# LOGIC_FPGA.net
KiCad netlist of a schematic drawn in Altium Designer
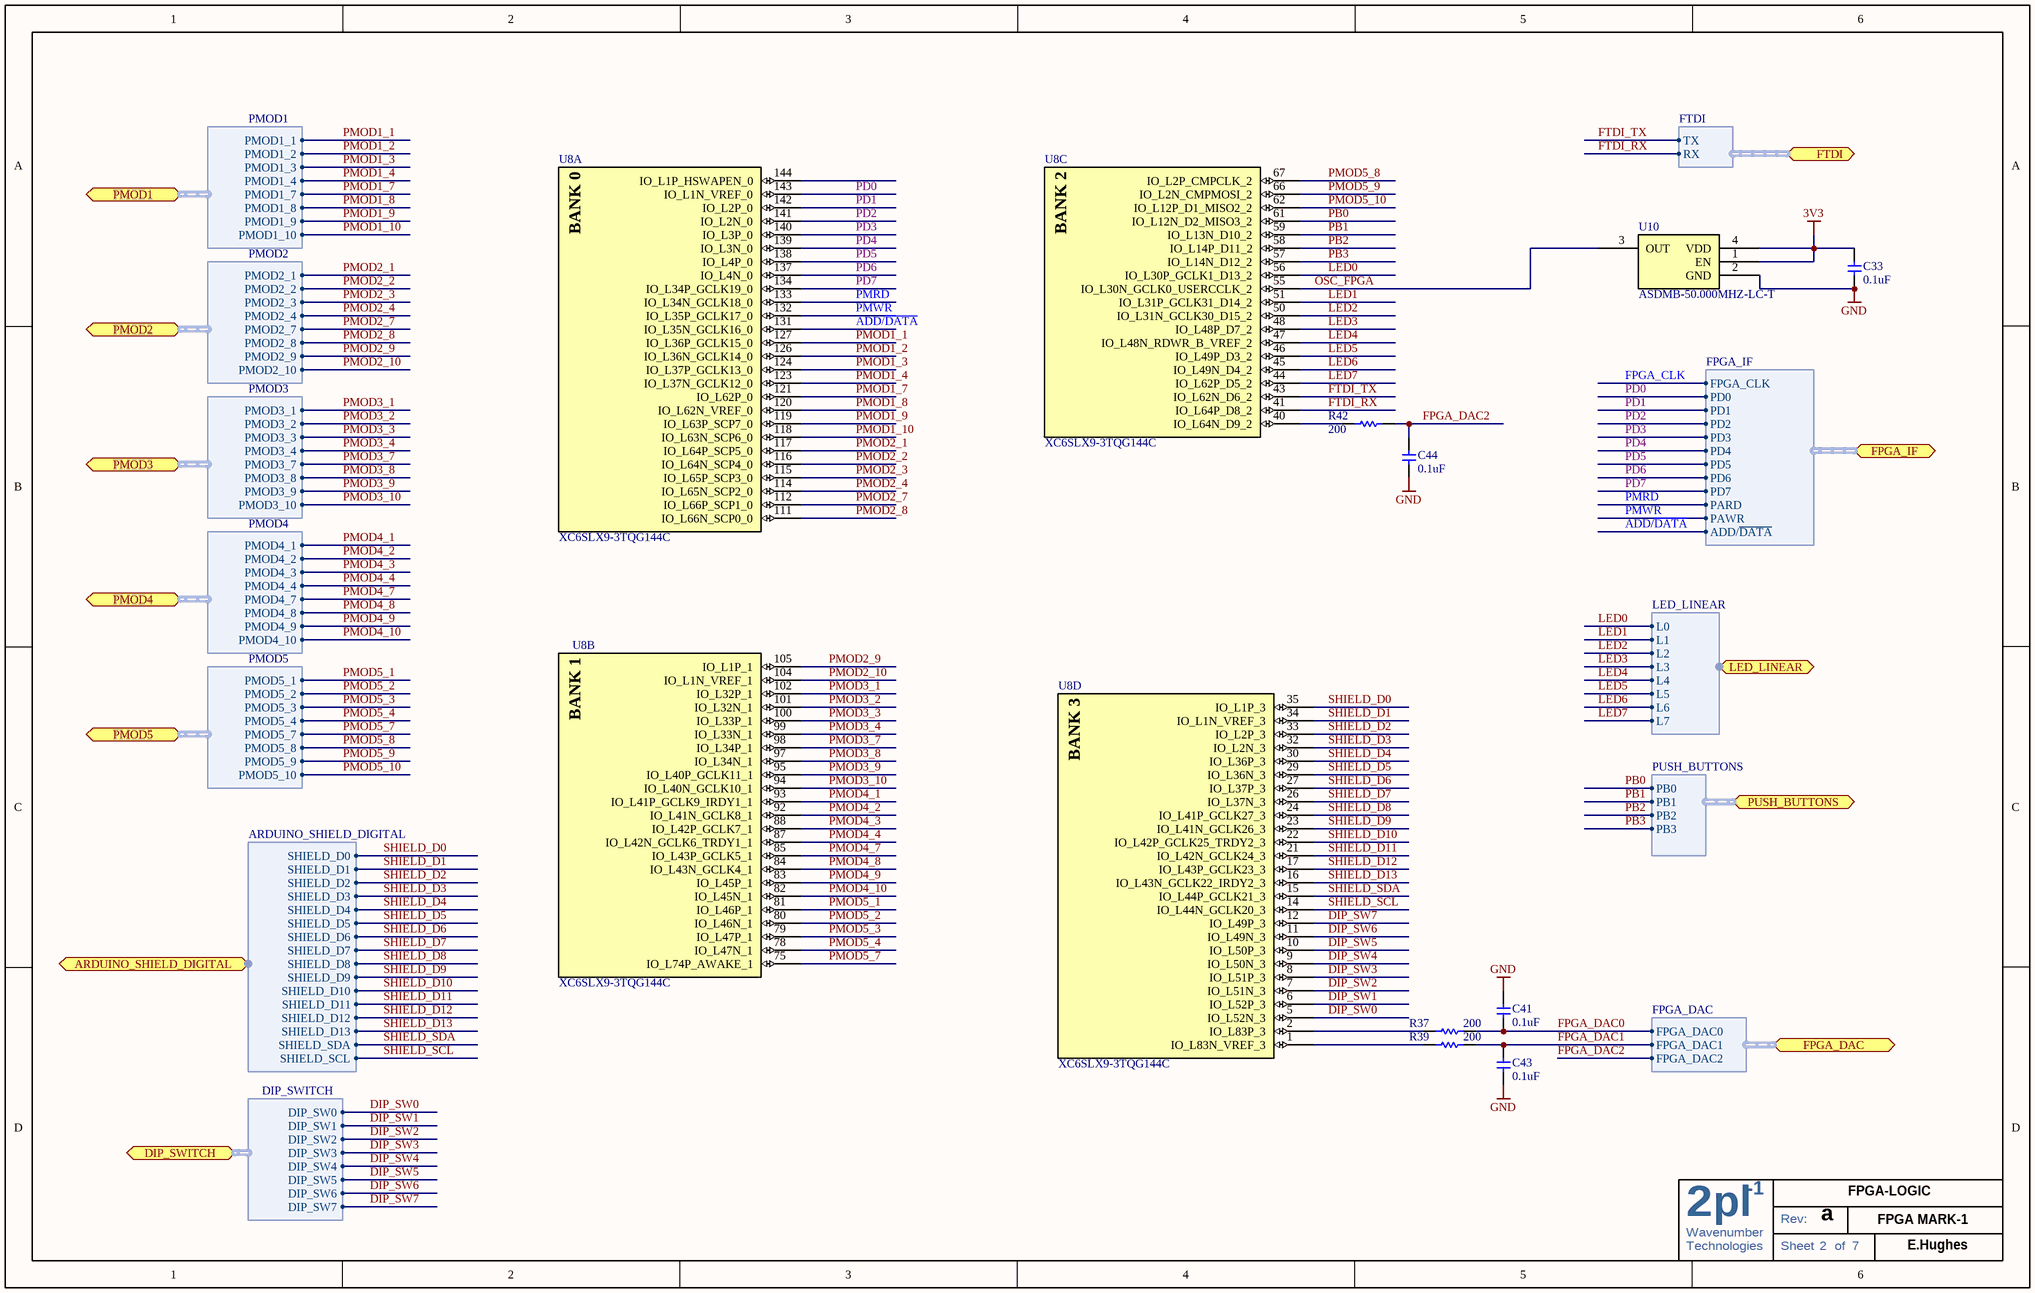
[diagram p0: LOGIC_FPGA.SchDoc]

(export (version "E")
  (design (tool "Eeschema 10.0.6"))
  (components
    (comp (ref "C33")
      (value "0.1uF")
      (footprint "C0603")
      (description "CAP CER .1UF 50V 10% X7R 0603")
      (fields
        (field (name "MANUFACTURER") "Murata Electronics North America")
        (field (name "MANUFACTURER PART NUMBER") "GRM188R71H104KA93D")
      )
      (libsource (lib "eCapacitors") (part "GRM188R71H104KA93D"))
    )
    (comp (ref "C41")
      (value "0.1uF")
      (footprint "C0603")
      (description "CAP CER .1UF 50V 10% X7R 0603")
      (fields
        (field (name "MANUFACTURER") "Murata Electronics North America")
        (field (name "MANUFACTURER PART NUMBER") "GRM188R71H104KA93D")
      )
      (libsource (lib "Capacitors") (part "GRM188R71H104KA93D"))
    )
    (comp (ref "C43")
      (value "0.1uF")
      (footprint "C0603")
      (description "CAP CER .1UF 50V 10% X7R 0603")
      (fields
        (field (name "MANUFACTURER") "Murata Electronics North America")
        (field (name "MANUFACTURER PART NUMBER") "GRM188R71H104KA93D")
      )
      (libsource (lib "Capacitors") (part "GRM188R71H104KA93D"))
    )
    (comp (ref "C44")
      (value "0.1uF")
      (footprint "C0603")
      (description "CAP CER .1UF 50V 10% X7R 0603")
      (fields
        (field (name "MANUFACTURER") "Murata Electronics North America")
        (field (name "MANUFACTURER PART NUMBER") "GRM188R71H104KA93D")
      )
      (libsource (lib "Capacitors") (part "GRM188R71H104KA93D"))
    )
    (comp (ref "R37")
      (value "200")
      (footprint "R0603")
      (description "RES 200 OHM 1/10W 1% 0603 SMD")
      (fields
        (field (name "MANUFACTURER") "Panasonic - ECG")
        (field (name "MANUFACTURER PART NUMBER") "ERJ-3EKF2000V")
      )
      (libsource (lib "eResistors") (part "ERJ-3EKF2000V"))
    )
    (comp (ref "R39")
      (value "200")
      (footprint "R0603")
      (description "RES 200 OHM 1/10W 1% 0603 SMD")
      (fields
        (field (name "MANUFACTURER") "Panasonic - ECG")
        (field (name "MANUFACTURER PART NUMBER") "ERJ-3EKF2000V")
      )
      (libsource (lib "eResistors") (part "ERJ-3EKF2000V"))
    )
    (comp (ref "R42")
      (value "200")
      (footprint "R0603")
      (description "RES 200 OHM 1/10W 1% 0603 SMD")
      (fields
        (field (name "MANUFACTURER") "Panasonic - ECG")
        (field (name "MANUFACTURER PART NUMBER") "ERJ-3EKF2000V")
      )
      (libsource (lib "eResistors") (part "ERJ-3EKF2000V"))
    )
    (comp (ref "U8")
      (value "XC6SLX9-3TQG144C")
      (footprint "TQ144_L")
      (description "IC FPAG SPARTAN 6 9K 144TQFP")
      (fields (field (name "MANUFACTURER") "Xilinx Inc"))
      (libsource (lib "eIC") (part "XC6SLX9-3TQG144C"))
    )
    (comp (ref "U10")
      (value "ASDMB-50.000MHZ-LC-T")
      (footprint "ASDMB - osc")
      (description "OSC MEMS 50.000 MHZ SMD")
      (fields (field (name "MANUFACTURER") "Abracon Corporation"))
      (libsource (lib "eIC") (part "ASDMB-50.000MHZ-LC-T"))
    )
  )
  (nets
    (net (code "13") (name "/ADD{slash}~{DATA}") (class "Default")
      (node (ref "U8") (pin "131") (pinfunction "IO_L35N_GCLK16_0_131") (pintype "bidirectional"))
    )
    (net (code "14") (name "/DIP_SW0") (class "Default")
      (node (ref "U8") (pin "5") (pinfunction "IO_L52N_3_5") (pintype "bidirectional"))
    )
    (net (code "15") (name "/DIP_SW1") (class "Default")
      (node (ref "U8") (pin "6") (pinfunction "IO_L52P_3_6") (pintype "bidirectional"))
    )
    (net (code "16") (name "/DIP_SW2") (class "Default")
      (node (ref "U8") (pin "7") (pinfunction "IO_L51N_3_7") (pintype "bidirectional"))
    )
    (net (code "17") (name "/DIP_SW3") (class "Default")
      (node (ref "U8") (pin "8") (pinfunction "IO_L51P_3_8") (pintype "bidirectional"))
    )
    (net (code "18") (name "/DIP_SW4") (class "Default")
      (node (ref "U8") (pin "9") (pinfunction "IO_L50N_3_9") (pintype "bidirectional"))
    )
    (net (code "19") (name "/DIP_SW5") (class "Default")
      (node (ref "U8") (pin "10") (pinfunction "IO_L50P_3_10") (pintype "bidirectional"))
    )
    (net (code "20") (name "/DIP_SW6") (class "Default")
      (node (ref "U8") (pin "11") (pinfunction "IO_L49N_3_11") (pintype "bidirectional"))
    )
    (net (code "21") (name "/DIP_SW7") (class "Default")
      (node (ref "U8") (pin "12") (pinfunction "IO_L49P_3_12") (pintype "bidirectional"))
    )
    (net (code "23") (name "/FPGA_DAC0") (class "Default")
      (node (ref "C41") (pin "1") (pinfunction "1_1") (pintype "passive"))
      (node (ref "R37") (pin "1") (pinfunction "1_1") (pintype "passive"))
    )
    (net (code "24") (name "/FPGA_DAC1") (class "Default")
      (node (ref "C43") (pin "1") (pinfunction "1_1") (pintype "passive"))
      (node (ref "R39") (pin "1") (pinfunction "1_1") (pintype "passive"))
    )
    (net (code "25") (name "/FPGA_DAC2") (class "Default")
      (node (ref "C44") (pin "1") (pinfunction "1_1") (pintype "passive"))
      (node (ref "R42") (pin "1") (pinfunction "1_1") (pintype "passive"))
    )
    (net (code "26") (name "/FTDI_RX") (class "Default")
      (node (ref "U8") (pin "41") (pinfunction "IO_L64P_D8_2_41") (pintype "bidirectional"))
    )
    (net (code "27") (name "/FTDI_TX") (class "Default")
      (node (ref "U8") (pin "43") (pinfunction "IO_L62N_D6_2_43") (pintype "bidirectional"))
    )
    (net (code "28") (name "/LED0") (class "Default")
      (node (ref "U8") (pin "56") (pinfunction "IO_L30P_GCLK1_D13_2_56") (pintype "bidirectional"))
    )
    (net (code "29") (name "/LED1") (class "Default")
      (node (ref "U8") (pin "51") (pinfunction "IO_L31P_GCLK31_D14_2_51") (pintype "bidirectional"))
    )
    (net (code "30") (name "/LED2") (class "Default")
      (node (ref "U8") (pin "50") (pinfunction "IO_L31N_GCLK30_D15_2_50") (pintype "bidirectional"))
    )
    (net (code "31") (name "/LED3") (class "Default")
      (node (ref "U8") (pin "48") (pinfunction "IO_L48P_D7_2_48") (pintype "bidirectional"))
    )
    (net (code "32") (name "/LED4") (class "Default")
      (node (ref "U8") (pin "47") (pinfunction "IO_L48N_RDWR_B_VREF_2_47") (pintype "bidirectional"))
    )
    (net (code "33") (name "/LED5") (class "Default")
      (node (ref "U8") (pin "46") (pinfunction "IO_L49P_D3_2_46") (pintype "bidirectional"))
    )
    (net (code "34") (name "/LED6") (class "Default")
      (node (ref "U8") (pin "45") (pinfunction "IO_L49N_D4_2_45") (pintype "bidirectional"))
    )
    (net (code "35") (name "/LED7") (class "Default")
      (node (ref "U8") (pin "44") (pinfunction "IO_L62P_D5_2_44") (pintype "bidirectional"))
    )
    (net (code "36") (name "/OSC_FPGA") (class "Default")
      (node (ref "U10") (pin "3") (pinfunction "OUT_3") (pintype "passive"))
      (node (ref "U8") (pin "55") (pinfunction "IO_L30N_GCLK0_USERCCLK_2_55") (pintype "bidirectional"))
    )
    (net (code "37") (name "/PB0") (class "Default")
      (node (ref "U8") (pin "61") (pinfunction "IO_L12N_D2_MISO3_2_61") (pintype "bidirectional"))
    )
    (net (code "38") (name "/PB1") (class "Default")
      (node (ref "U8") (pin "59") (pinfunction "IO_L13N_D10_2_59") (pintype "bidirectional"))
    )
    (net (code "39") (name "/PB2") (class "Default")
      (node (ref "U8") (pin "58") (pinfunction "IO_L14P_D11_2_58") (pintype "bidirectional"))
    )
    (net (code "40") (name "/PB3") (class "Default")
      (node (ref "U8") (pin "57") (pinfunction "IO_L14N_D12_2_57") (pintype "bidirectional"))
    )
    (net (code "41") (name "/PD0") (class "Default")
      (node (ref "U8") (pin "143") (pinfunction "IO_L1N_VREF_0_143") (pintype "bidirectional"))
    )
    (net (code "42") (name "/PD1") (class "Default")
      (node (ref "U8") (pin "142") (pinfunction "IO_L2P_0_142") (pintype "bidirectional"))
    )
    (net (code "43") (name "/PD2") (class "Default")
      (node (ref "U8") (pin "141") (pinfunction "IO_L2N_0_141") (pintype "bidirectional"))
    )
    (net (code "44") (name "/PD3") (class "Default")
      (node (ref "U8") (pin "140") (pinfunction "IO_L3P_0_140") (pintype "bidirectional"))
    )
    (net (code "45") (name "/PD4") (class "Default")
      (node (ref "U8") (pin "139") (pinfunction "IO_L3N_0_139") (pintype "bidirectional"))
    )
    (net (code "46") (name "/PD5") (class "Default")
      (node (ref "U8") (pin "138") (pinfunction "IO_L4P_0_138") (pintype "bidirectional"))
    )
    (net (code "47") (name "/PD6") (class "Default")
      (node (ref "U8") (pin "137") (pinfunction "IO_L4N_0_137") (pintype "bidirectional"))
    )
    (net (code "48") (name "/PD7") (class "Default")
      (node (ref "U8") (pin "134") (pinfunction "IO_L34P_GCLK19_0_134") (pintype "bidirectional"))
    )
    (net (code "49") (name "/PMOD1_1") (class "Default")
      (node (ref "U8") (pin "127") (pinfunction "IO_L36P_GCLK15_0_127") (pintype "bidirectional"))
    )
    (net (code "50") (name "/PMOD1_2") (class "Default")
      (node (ref "U8") (pin "126") (pinfunction "IO_L36N_GCLK14_0_126") (pintype "bidirectional"))
    )
    (net (code "51") (name "/PMOD1_3") (class "Default")
      (node (ref "U8") (pin "124") (pinfunction "IO_L37P_GCLK13_0_124") (pintype "bidirectional"))
    )
    (net (code "52") (name "/PMOD1_4") (class "Default")
      (node (ref "U8") (pin "123") (pinfunction "IO_L37N_GCLK12_0_123") (pintype "bidirectional"))
    )
    (net (code "53") (name "/PMOD1_7") (class "Default")
      (node (ref "U8") (pin "121") (pinfunction "IO_L62P_0_121") (pintype "bidirectional"))
    )
    (net (code "54") (name "/PMOD1_8") (class "Default")
      (node (ref "U8") (pin "120") (pinfunction "IO_L62N_VREF_0_120") (pintype "bidirectional"))
    )
    (net (code "55") (name "/PMOD1_9") (class "Default")
      (node (ref "U8") (pin "119") (pinfunction "IO_L63P_SCP7_0_119") (pintype "bidirectional"))
    )
    (net (code "56") (name "/PMOD1_10") (class "Default")
      (node (ref "U8") (pin "118") (pinfunction "IO_L63N_SCP6_0_118") (pintype "bidirectional"))
    )
    (net (code "57") (name "/PMOD2_1") (class "Default")
      (node (ref "U8") (pin "117") (pinfunction "IO_L64P_SCP5_0_117") (pintype "bidirectional"))
    )
    (net (code "58") (name "/PMOD2_2") (class "Default")
      (node (ref "U8") (pin "116") (pinfunction "IO_L64N_SCP4_0_116") (pintype "bidirectional"))
    )
    (net (code "59") (name "/PMOD2_3") (class "Default")
      (node (ref "U8") (pin "115") (pinfunction "IO_L65P_SCP3_0_115") (pintype "bidirectional"))
    )
    (net (code "60") (name "/PMOD2_4") (class "Default")
      (node (ref "U8") (pin "114") (pinfunction "IO_L65N_SCP2_0_114") (pintype "bidirectional"))
    )
    (net (code "61") (name "/PMOD2_7") (class "Default")
      (node (ref "U8") (pin "112") (pinfunction "IO_L66P_SCP1_0_112") (pintype "bidirectional"))
    )
    (net (code "62") (name "/PMOD2_8") (class "Default")
      (node (ref "U8") (pin "111") (pinfunction "IO_L66N_SCP0_0_111") (pintype "bidirectional"))
    )
    (net (code "63") (name "/PMOD2_9") (class "Default")
      (node (ref "U8") (pin "105") (pinfunction "IO_L1P_1_105") (pintype "bidirectional"))
    )
    (net (code "64") (name "/PMOD2_10") (class "Default")
      (node (ref "U8") (pin "104") (pinfunction "IO_L1N_VREF_1_104") (pintype "bidirectional"))
    )
    (net (code "65") (name "/PMOD3_1") (class "Default")
      (node (ref "U8") (pin "102") (pinfunction "IO_L32P_1_102") (pintype "bidirectional"))
    )
    (net (code "66") (name "/PMOD3_2") (class "Default")
      (node (ref "U8") (pin "101") (pinfunction "IO_L32N_1_101") (pintype "bidirectional"))
    )
    (net (code "67") (name "/PMOD3_3") (class "Default")
      (node (ref "U8") (pin "100") (pinfunction "IO_L33P_1_100") (pintype "bidirectional"))
    )
    (net (code "68") (name "/PMOD3_4") (class "Default")
      (node (ref "U8") (pin "99") (pinfunction "IO_L33N_1_99") (pintype "bidirectional"))
    )
    (net (code "69") (name "/PMOD3_7") (class "Default")
      (node (ref "U8") (pin "98") (pinfunction "IO_L34P_1_98") (pintype "bidirectional"))
    )
    (net (code "70") (name "/PMOD3_8") (class "Default")
      (node (ref "U8") (pin "97") (pinfunction "IO_L34N_1_97") (pintype "bidirectional"))
    )
    (net (code "71") (name "/PMOD3_9") (class "Default")
      (node (ref "U8") (pin "95") (pinfunction "IO_L40P_GCLK11_1_95") (pintype "bidirectional"))
    )
    (net (code "72") (name "/PMOD3_10") (class "Default")
      (node (ref "U8") (pin "94") (pinfunction "IO_L40N_GCLK10_1_94") (pintype "bidirectional"))
    )
    (net (code "73") (name "/PMOD4_1") (class "Default")
      (node (ref "U8") (pin "93") (pinfunction "IO_L41P_GCLK9_IRDY1_1_93") (pintype "bidirectional"))
    )
    (net (code "74") (name "/PMOD4_2") (class "Default")
      (node (ref "U8") (pin "92") (pinfunction "IO_L41N_GCLK8_1_92") (pintype "bidirectional"))
    )
    (net (code "75") (name "/PMOD4_3") (class "Default")
      (node (ref "U8") (pin "88") (pinfunction "IO_L42P_GCLK7_1_88") (pintype "bidirectional"))
    )
    (net (code "76") (name "/PMOD4_4") (class "Default")
      (node (ref "U8") (pin "87") (pinfunction "IO_L42N_GCLK6_TRDY1_1_87") (pintype "bidirectional"))
    )
    (net (code "77") (name "/PMOD4_7") (class "Default")
      (node (ref "U8") (pin "85") (pinfunction "IO_L43P_GCLK5_1_85") (pintype "bidirectional"))
    )
    (net (code "78") (name "/PMOD4_8") (class "Default")
      (node (ref "U8") (pin "84") (pinfunction "IO_L43N_GCLK4_1_84") (pintype "bidirectional"))
    )
    (net (code "79") (name "/PMOD4_9") (class "Default")
      (node (ref "U8") (pin "83") (pinfunction "IO_L45P_1_83") (pintype "bidirectional"))
    )
    (net (code "80") (name "/PMOD4_10") (class "Default")
      (node (ref "U8") (pin "82") (pinfunction "IO_L45N_1_82") (pintype "bidirectional"))
    )
    (net (code "81") (name "/PMOD5_1") (class "Default")
      (node (ref "U8") (pin "81") (pinfunction "IO_L46P_1_81") (pintype "bidirectional"))
    )
    (net (code "82") (name "/PMOD5_2") (class "Default")
      (node (ref "U8") (pin "80") (pinfunction "IO_L46N_1_80") (pintype "bidirectional"))
    )
    (net (code "83") (name "/PMOD5_3") (class "Default")
      (node (ref "U8") (pin "79") (pinfunction "IO_L47P_1_79") (pintype "bidirectional"))
    )
    (net (code "84") (name "/PMOD5_4") (class "Default")
      (node (ref "U8") (pin "78") (pinfunction "IO_L47N_1_78") (pintype "bidirectional"))
    )
    (net (code "85") (name "/PMOD5_7") (class "Default")
      (node (ref "U8") (pin "75") (pinfunction "IO_L74P_AWAKE_1_75") (pintype "bidirectional"))
    )
    (net (code "86") (name "/PMOD5_8") (class "Default")
      (node (ref "U8") (pin "67") (pinfunction "IO_L2P_CMPCLK_2_67") (pintype "bidirectional"))
    )
    (net (code "87") (name "/PMOD5_9") (class "Default")
      (node (ref "U8") (pin "66") (pinfunction "IO_L2N_CMPMOSI_2_66") (pintype "bidirectional"))
    )
    (net (code "88") (name "/PMOD5_10") (class "Default")
      (node (ref "U8") (pin "62") (pinfunction "IO_L12P_D1_MISO2_2_62") (pintype "bidirectional"))
    )
    (net (code "89") (name "/PMRD") (class "Default")
      (node (ref "U8") (pin "133") (pinfunction "IO_L34N_GCLK18_0_133") (pintype "bidirectional"))
    )
    (net (code "90") (name "/PMWR") (class "Default")
      (node (ref "U8") (pin "132") (pinfunction "IO_L35P_GCLK17_0_132") (pintype "bidirectional"))
    )
    (net (code "91") (name "/SHIELD_D0") (class "Default")
      (node (ref "U8") (pin "35") (pinfunction "IO_L1P_3_35") (pintype "bidirectional"))
    )
    (net (code "92") (name "/SHIELD_D1") (class "Default")
      (node (ref "U8") (pin "34") (pinfunction "IO_L1N_VREF_3_34") (pintype "bidirectional"))
    )
    (net (code "93") (name "/SHIELD_D2") (class "Default")
      (node (ref "U8") (pin "33") (pinfunction "IO_L2P_3_33") (pintype "bidirectional"))
    )
    (net (code "94") (name "/SHIELD_D3") (class "Default")
      (node (ref "U8") (pin "32") (pinfunction "IO_L2N_3_32") (pintype "bidirectional"))
    )
    (net (code "95") (name "/SHIELD_D4") (class "Default")
      (node (ref "U8") (pin "30") (pinfunction "IO_L36P_3_30") (pintype "bidirectional"))
    )
    (net (code "96") (name "/SHIELD_D5") (class "Default")
      (node (ref "U8") (pin "29") (pinfunction "IO_L36N_3_29") (pintype "bidirectional"))
    )
    (net (code "97") (name "/SHIELD_D6") (class "Default")
      (node (ref "U8") (pin "27") (pinfunction "IO_L37P_3_27") (pintype "bidirectional"))
    )
    (net (code "98") (name "/SHIELD_D7") (class "Default")
      (node (ref "U8") (pin "26") (pinfunction "IO_L37N_3_26") (pintype "bidirectional"))
    )
    (net (code "99") (name "/SHIELD_D8") (class "Default")
      (node (ref "U8") (pin "24") (pinfunction "IO_L41P_GCLK27_3_24") (pintype "bidirectional"))
    )
    (net (code "100") (name "/SHIELD_D9") (class "Default")
      (node (ref "U8") (pin "23") (pinfunction "IO_L41N_GCLK26_3_23") (pintype "bidirectional"))
    )
    (net (code "101") (name "/SHIELD_D10") (class "Default")
      (node (ref "U8") (pin "22") (pinfunction "IO_L42P_GCLK25_TRDY2_3_22") (pintype "bidirectional"))
    )
    (net (code "102") (name "/SHIELD_D11") (class "Default")
      (node (ref "U8") (pin "21") (pinfunction "IO_L42N_GCLK24_3_21") (pintype "bidirectional"))
    )
    (net (code "103") (name "/SHIELD_D12") (class "Default")
      (node (ref "U8") (pin "17") (pinfunction "IO_L43P_GCLK23_3_17") (pintype "bidirectional"))
    )
    (net (code "104") (name "/SHIELD_D13") (class "Default")
      (node (ref "U8") (pin "16") (pinfunction "IO_L43N_GCLK22_IRDY2_3_16") (pintype "bidirectional"))
    )
    (net (code "105") (name "/SHIELD_SCL") (class "Default")
      (node (ref "U8") (pin "14") (pinfunction "IO_L44N_GCLK20_3_14") (pintype "bidirectional"))
    )
    (net (code "106") (name "/SHIELD_SDA") (class "Default")
      (node (ref "U8") (pin "15") (pinfunction "IO_L44P_GCLK21_3_15") (pintype "bidirectional"))
    )
    (net (code "119") (name "3V3") (class "Default")
      (node (ref "C33") (pin "2") (pinfunction "2_2") (pintype "passive"))
      (node (ref "U10") (pin "1") (pinfunction "EN_1") (pintype "passive"))
      (node (ref "U10") (pin "4") (pinfunction "VDD_4") (pintype "passive"))
    )
    (net (code "120") (name "GND") (class "Default")
      (node (ref "C33") (pin "1") (pinfunction "1_1") (pintype "passive"))
      (node (ref "C41") (pin "2") (pinfunction "2_2") (pintype "passive"))
      (node (ref "C43") (pin "2") (pinfunction "2_2") (pintype "passive"))
      (node (ref "C44") (pin "2") (pinfunction "2_2") (pintype "passive"))
      (node (ref "U10") (pin "2") (pinfunction "GND_2") (pintype "passive"))
    )
    (net (code "121") (name "Net-(U8C-IO_L64N_D9_2)") (class "Default")
      (node (ref "R42") (pin "2") (pinfunction "2_2") (pintype "passive"))
      (node (ref "U8") (pin "40") (pinfunction "IO_L64N_D9_2_40") (pintype "bidirectional"))
    )
    (net (code "122") (name "Net-(U8D-IO_L83N_VREF_3)") (class "Default")
      (node (ref "R39") (pin "2") (pinfunction "2_2") (pintype "passive"))
      (node (ref "U8") (pin "1") (pinfunction "IO_L83N_VREF_3_1") (pintype "bidirectional"))
    )
    (net (code "123") (name "Net-(U8D-IO_L83P_3)") (class "Default")
      (node (ref "R37") (pin "2") (pinfunction "2_2") (pintype "passive"))
      (node (ref "U8") (pin "2") (pinfunction "IO_L83P_3_2") (pintype "bidirectional"))
    )
    (net (code "124") (name "unconnected-(U8A-IO_L1P_HSWAPEN_0-Pad144)") (class "Default")
      (node (ref "U8") (pin "144") (pinfunction "IO_L1P_HSWAPEN_0_144") (pintype "bidirectional"))
    )
  )
)
